# P450_FJ_P_A_V2_3_F.net
KiCad netlist of a schematic drawn in Altium Designer
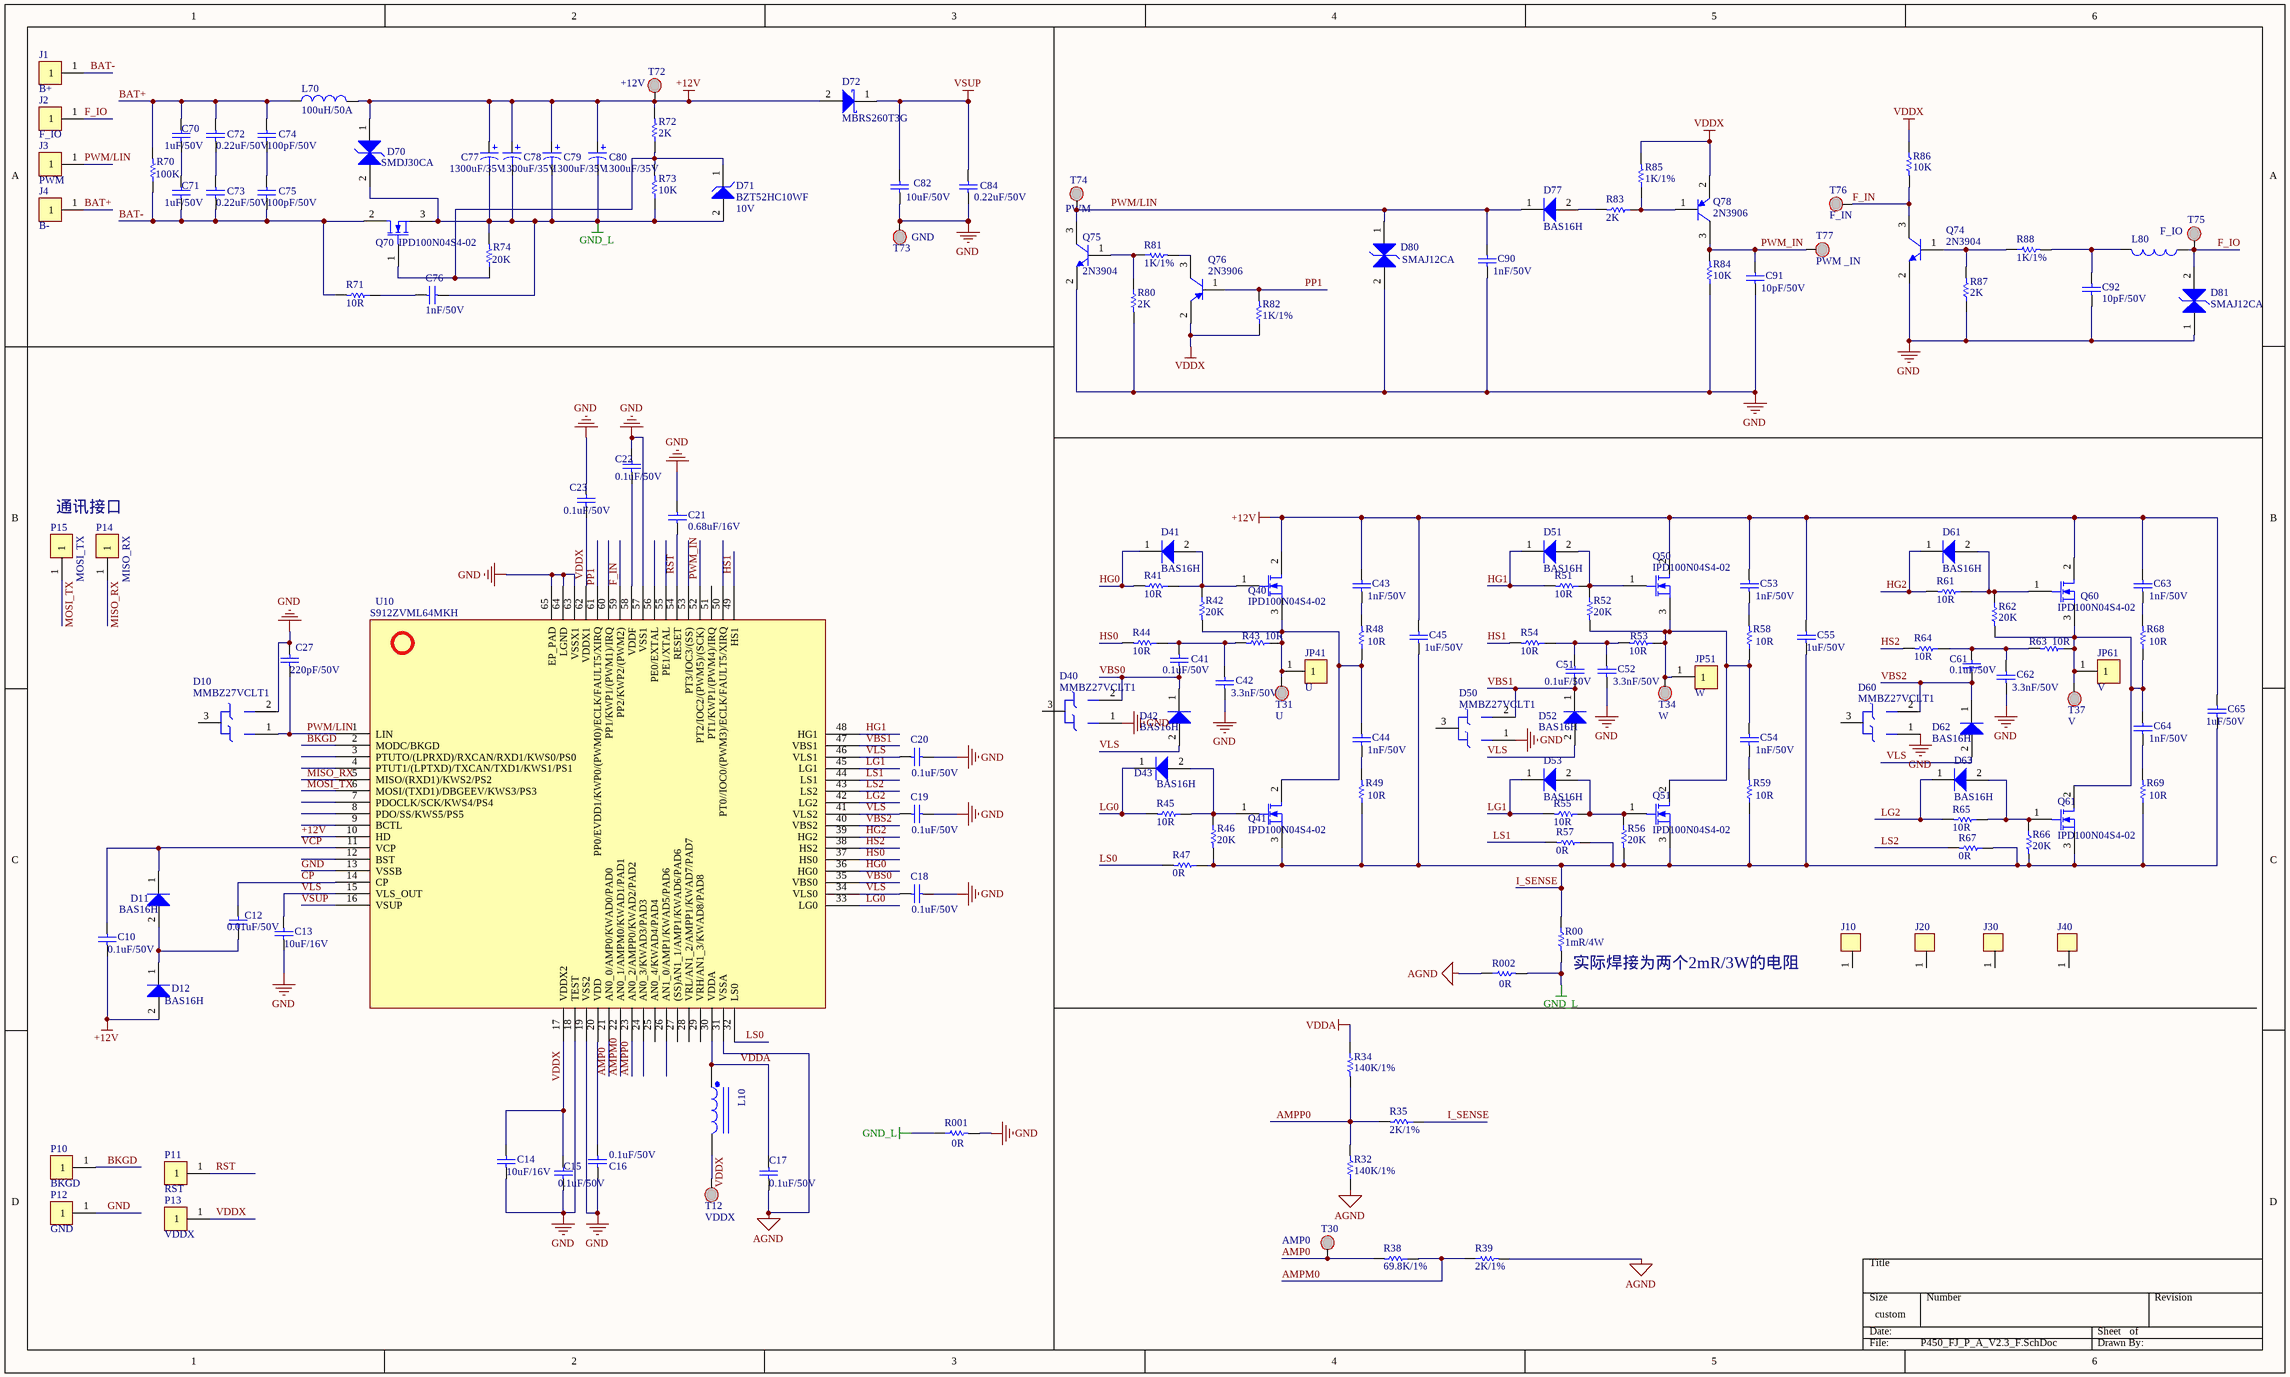
[diagram p0: P450_FJ_P_A_V2.3_F.SchDoc]

(export (version "E")
  (design (tool "Eeschema 10.0.6"))
  (components
    (comp (ref "C10")
      (value "0.1uF/50V")
      (footprint "0603")
      (description "Capacitor")
      (fields (field (name "PUBLISHER") "Altium Limited"))
      (libsource (lib "Miscellaneous Devices") (part "Cap"))
    )
    (comp (ref "C12")
      (value "0.01uF/50V")
      (footprint "0603")
      (description "Capacitor")
      (fields (field (name "PUBLISHER") "Altium Limited"))
      (libsource (lib "Miscellaneous Devices") (part "Cap"))
    )
    (comp (ref "C13")
      (value "10uF/16V")
      (footprint "0805")
      (description "Capacitor")
      (fields (field (name "PUBLISHER") "Altium Limited"))
      (libsource (lib "Miscellaneous Devices") (part "Cap"))
    )
    (comp (ref "C14")
      (value "10uF/16V")
      (footprint "0805")
      (description "Capacitor")
      (fields (field (name "PUBLISHER") "Altium Limited"))
      (libsource (lib "Miscellaneous Devices") (part "Cap"))
    )
    (comp (ref "C15")
      (value "0.1uF/50V")
      (footprint "0603")
      (description "Capacitor")
      (fields (field (name "PUBLISHER") "Altium Limited"))
      (libsource (lib "Miscellaneous Devices") (part "Cap"))
    )
    (comp (ref "C16")
      (value "0.1uF/50V")
      (footprint "0603")
      (description "Capacitor")
      (fields (field (name "PUBLISHER") "Altium Limited"))
      (libsource (lib "Miscellaneous Devices") (part "Cap"))
    )
    (comp (ref "C17")
      (value "0.1uF/50V")
      (footprint "0603")
      (description "Capacitor")
      (fields (field (name "PUBLISHER") "Altium Limited"))
      (libsource (lib "Miscellaneous Devices") (part "Cap"))
    )
    (comp (ref "C18")
      (value "0.1uF/50V")
      (footprint "0603")
      (description "Capacitor")
      (fields (field (name "PUBLISHER") "Altium Limited"))
      (libsource (lib "Miscellaneous Devices") (part "Cap"))
    )
    (comp (ref "C19")
      (value "0.1uF/50V")
      (footprint "0603")
      (description "Capacitor")
      (fields (field (name "PUBLISHER") "Altium Limited"))
      (libsource (lib "Miscellaneous Devices") (part "Cap"))
    )
    (comp (ref "C20")
      (value "0.1uF/50V")
      (footprint "0603")
      (description "Capacitor")
      (fields (field (name "PUBLISHER") "Altium Limited"))
      (libsource (lib "Miscellaneous Devices") (part "Cap"))
    )
    (comp (ref "C21")
      (value "0.68uF/16V")
      (footprint "0603")
      (description "Capacitor")
      (fields (field (name "PUBLISHER") "Altium Limited"))
      (libsource (lib "Miscellaneous Devices") (part "Cap"))
    )
    (comp (ref "C22")
      (value "0.1uF/50V")
      (footprint "0603")
      (description "Capacitor")
      (fields (field (name "PUBLISHER") "Altium Limited"))
      (libsource (lib "Miscellaneous Devices") (part "Cap"))
    )
    (comp (ref "C23")
      (value "0.1uF/50V")
      (footprint "0603")
      (description "Capacitor")
      (fields (field (name "PUBLISHER") "Altium Limited"))
      (libsource (lib "Miscellaneous Devices") (part "Cap"))
    )
    (comp (ref "C27")
      (value "220pF/50V")
      (footprint "0603")
      (description "Capacitor")
      (fields (field (name "PUBLISHER") "Altium Limited"))
      (libsource (lib "Miscellaneous Devices") (part "Cap"))
    )
    (comp (ref "C41")
      (value "0.1uF/50V")
      (footprint "0603")
      (description "Capacitor")
      (fields (field (name "PUBLISHER") "Altium Limited"))
      (libsource (lib "Miscellaneous Devices") (part "Cap"))
    )
    (comp (ref "C42")
      (value "3.3nF/50V")
      (footprint "0603")
      (description "Capacitor")
      (fields (field (name "PUBLISHER") "Altium Limited"))
      (libsource (lib "Miscellaneous Devices") (part "Cap"))
    )
    (comp (ref "C43")
      (value "1nF/50V")
      (footprint "0603")
      (description "Capacitor")
      (fields (field (name "PUBLISHER") "Altium Limited"))
      (libsource (lib "Miscellaneous Devices") (part "Cap"))
    )
    (comp (ref "C44")
      (value "1nF/50V")
      (footprint "0603")
      (description "Capacitor")
      (fields (field (name "PUBLISHER") "Altium Limited"))
      (libsource (lib "Miscellaneous Devices") (part "Cap"))
    )
    (comp (ref "C45")
      (value "1uF/50V")
      (footprint "0805")
      (description "Capacitor")
      (fields (field (name "PUBLISHER") "Altium Limited"))
      (libsource (lib "Miscellaneous Devices") (part "Cap"))
    )
    (comp (ref "C51")
      (value "0.1uF/50V")
      (footprint "0603")
      (description "Capacitor")
      (fields (field (name "PUBLISHER") "Altium Limited"))
      (libsource (lib "Miscellaneous Devices") (part "Cap"))
    )
    (comp (ref "C52")
      (value "3.3nF/50V")
      (footprint "0603")
      (description "Capacitor")
      (fields (field (name "PUBLISHER") "Altium Limited"))
      (libsource (lib "Miscellaneous Devices") (part "Cap"))
    )
    (comp (ref "C53")
      (value "1nF/50V")
      (footprint "0603")
      (description "Capacitor")
      (fields (field (name "PUBLISHER") "Altium Limited"))
      (libsource (lib "Miscellaneous Devices") (part "Cap"))
    )
    (comp (ref "C54")
      (value "1nF/50V")
      (footprint "0603")
      (description "Capacitor")
      (fields (field (name "PUBLISHER") "Altium Limited"))
      (libsource (lib "Miscellaneous Devices") (part "Cap"))
    )
    (comp (ref "C55")
      (value "1uF/50V")
      (footprint "0805")
      (description "Capacitor")
      (fields (field (name "PUBLISHER") "Altium Limited"))
      (libsource (lib "Miscellaneous Devices") (part "Cap"))
    )
    (comp (ref "C61")
      (value "0.1uF/50V")
      (footprint "0603")
      (description "Capacitor")
      (fields (field (name "PUBLISHER") "Altium Limited"))
      (libsource (lib "Miscellaneous Devices") (part "Cap"))
    )
    (comp (ref "C62")
      (value "3.3nF/50V")
      (footprint "0603")
      (description "Capacitor")
      (fields (field (name "PUBLISHER") "Altium Limited"))
      (libsource (lib "Miscellaneous Devices") (part "Cap"))
    )
    (comp (ref "C63")
      (value "1nF/50V")
      (footprint "0603")
      (description "Capacitor")
      (fields (field (name "PUBLISHER") "Altium Limited"))
      (libsource (lib "Miscellaneous Devices") (part "Cap"))
    )
    (comp (ref "C64")
      (value "1nF/50V")
      (footprint "0603")
      (description "Capacitor")
      (fields (field (name "PUBLISHER") "Altium Limited"))
      (libsource (lib "Miscellaneous Devices") (part "Cap"))
    )
    (comp (ref "C65")
      (value "1uF/50V")
      (footprint "0805")
      (description "Capacitor")
      (fields (field (name "PUBLISHER") "Altium Limited"))
      (libsource (lib "Miscellaneous Devices") (part "Cap"))
    )
    (comp (ref "C70")
      (value "1uF/50V")
      (footprint "0805")
      (description "Capacitor")
      (fields (field (name "PUBLISHER") "Altium Limited"))
      (libsource (lib "Miscellaneous Devices") (part "Cap"))
    )
    (comp (ref "C71")
      (value "1uF/50V")
      (footprint "0805")
      (description "Capacitor")
      (fields (field (name "PUBLISHER") "Altium Limited"))
      (libsource (lib "Miscellaneous Devices") (part "Cap"))
    )
    (comp (ref "C72")
      (value "0.22uF/50V")
      (footprint "0805")
      (description "Capacitor")
      (fields (field (name "PUBLISHER") "Altium Limited"))
      (libsource (lib "Miscellaneous Devices") (part "Cap"))
    )
    (comp (ref "C73")
      (value "0.22uF/50V")
      (footprint "0805")
      (description "Capacitor")
      (fields (field (name "PUBLISHER") "Altium Limited"))
      (libsource (lib "Miscellaneous Devices") (part "Cap"))
    )
    (comp (ref "C74")
      (value "100pF/50V")
      (footprint "0805")
      (description "Capacitor")
      (fields (field (name "PUBLISHER") "Altium Limited"))
      (libsource (lib "Miscellaneous Devices") (part "Cap"))
    )
    (comp (ref "C75")
      (value "100pF/50V")
      (footprint "0805")
      (description "Capacitor")
      (fields (field (name "PUBLISHER") "Altium Limited"))
      (libsource (lib "Miscellaneous Devices") (part "Cap"))
    )
    (comp (ref "C76")
      (value "1nF/50V")
      (footprint "0603")
      (description "Capacitor")
      (fields (field (name "PUBLISHER") "Altium Limited"))
      (libsource (lib "Miscellaneous Devices") (part "Cap"))
    )
    (comp (ref "C77")
      (value "1300uF/35V")
      (footprint "RB5.0")
      (description "EGPD350E__132MK20H")
      (fields (field (name "PUBLISHER") "Altium Limited"))
      (libsource (lib "Miscellaneous Devices") (part "Cap Pol1"))
    )
    (comp (ref "C78")
      (value "1300uF/35V")
      (footprint "RB5.0")
      (description "EGPD350E__132MK20H")
      (fields (field (name "PUBLISHER") "Altium Limited"))
      (libsource (lib "Miscellaneous Devices") (part "Cap Pol1"))
    )
    (comp (ref "C79")
      (value "1300uF/35V")
      (footprint "RB5.0")
      (description "EGPD350E__132MK20H")
      (fields (field (name "PUBLISHER") "Altium Limited"))
      (libsource (lib "Miscellaneous Devices") (part "Cap Pol1"))
    )
    (comp (ref "C80")
      (value "1300uF/35V")
      (footprint "RB5.0")
      (description "EGPD350E__132MK20H")
      (fields (field (name "PUBLISHER") "Altium Limited"))
      (libsource (lib "Miscellaneous Devices") (part "Cap Pol1"))
    )
    (comp (ref "C82")
      (value "10uF/50V")
      (footprint "1210")
      (description "Capacitor")
      (fields (field (name "PUBLISHER") "Altium Limited"))
      (libsource (lib "Miscellaneous Devices") (part "Cap"))
    )
    (comp (ref "C84")
      (value "0.22uF/50V")
      (footprint "0805")
      (description "Capacitor")
      (fields (field (name "PUBLISHER") "Altium Limited"))
      (libsource (lib "Miscellaneous Devices") (part "Cap"))
    )
    (comp (ref "C90")
      (value "1nF/50V")
      (footprint "0603")
      (description "Capacitor")
      (fields (field (name "PUBLISHER") "Altium Limited"))
      (libsource (lib "Miscellaneous Devices") (part "Cap"))
    )
    (comp (ref "C91")
      (value "10pF/50V")
      (footprint "0603")
      (description "Capacitor")
      (fields (field (name "PUBLISHER") "Altium Limited"))
      (libsource (lib "Miscellaneous Devices") (part "Cap"))
    )
    (comp (ref "C92")
      (value "10pF/50V")
      (footprint "0603")
      (description "Capacitor")
      (fields (field (name "PUBLISHER") "Altium Limited"))
      (libsource (lib "Miscellaneous Devices") (part "Cap"))
    )
    (comp (ref "D10")
      (value "MMBZ27VCLT1")
      (footprint "SOT-23T")
      (description "D_TVS")
      (libsource (lib "SCH_LIB") (part "MMBZ27VCLT1"))
    )
    (comp (ref "D11")
      (value "BAS16H")
      (footprint "SOD323")
      (description "Default Diode")
      (fields (field (name "PUBLISHER") "Altium Limited"))
      (libsource (lib "LIN_12V-3P") (part "Diode"))
    )
    (comp (ref "D12")
      (value "BAS16H")
      (footprint "SOD323")
      (description "Default Diode")
      (fields (field (name "PUBLISHER") "Altium Limited"))
      (libsource (lib "LIN_12V-3P") (part "Diode"))
    )
    (comp (ref "D40")
      (value "MMBZ27VCLT1")
      (footprint "SOT-23T")
      (description "D_TVS")
      (libsource (lib "SCH_LIB") (part "MMBZ27VCLT1"))
    )
    (comp (ref "D41")
      (value "BAS16H")
      (footprint "SOD323")
      (description "Default Diode")
      (fields (field (name "PUBLISHER") "Altium Limited"))
      (libsource (lib "LIN_12V-3P") (part "Diode"))
    )
    (comp (ref "D42")
      (value "BAS16H")
      (footprint "SOD323")
      (description "Default Diode")
      (fields (field (name "PUBLISHER") "Altium Limited"))
      (libsource (lib "LIN_12V-3P") (part "Diode"))
    )
    (comp (ref "D43")
      (value "BAS16H")
      (footprint "SOD323")
      (description "Default Diode")
      (fields (field (name "PUBLISHER") "Altium Limited"))
      (libsource (lib "LIN_12V-3P") (part "Diode"))
    )
    (comp (ref "D50")
      (value "MMBZ27VCLT1")
      (footprint "SOT-23T")
      (description "D_TVS")
      (libsource (lib "SCH_LIB") (part "MMBZ27VCLT1"))
    )
    (comp (ref "D51")
      (value "BAS16H")
      (footprint "SOD323")
      (description "Default Diode")
      (fields (field (name "PUBLISHER") "Altium Limited"))
      (libsource (lib "LIN_12V-3P") (part "Diode"))
    )
    (comp (ref "D52")
      (value "BAS16H")
      (footprint "SOD323")
      (description "Default Diode")
      (fields (field (name "PUBLISHER") "Altium Limited"))
      (libsource (lib "LIN_12V-3P") (part "Diode"))
    )
    (comp (ref "D53")
      (value "BAS16H")
      (footprint "SOD323")
      (description "Default Diode")
      (fields (field (name "PUBLISHER") "Altium Limited"))
      (libsource (lib "LIN_12V-3P") (part "Diode"))
    )
    (comp (ref "D60")
      (value "MMBZ27VCLT1")
      (footprint "SOT-23T")
      (description "D_TVS")
      (libsource (lib "SCH_LIB") (part "MMBZ27VCLT1"))
    )
    (comp (ref "D61")
      (value "BAS16H")
      (footprint "SOD323")
      (description "Default Diode")
      (fields (field (name "PUBLISHER") "Altium Limited"))
      (libsource (lib "LIN_12V-3P") (part "Diode"))
    )
    (comp (ref "D62")
      (value "BAS16H")
      (footprint "SOD323")
      (description "Default Diode")
      (fields (field (name "PUBLISHER") "Altium Limited"))
      (libsource (lib "LIN_12V-3P") (part "Diode"))
    )
    (comp (ref "D63")
      (value "BAS16H")
      (footprint "SOD323")
      (description "Default Diode")
      (fields (field (name "PUBLISHER") "Altium Limited"))
      (libsource (lib "LIN_12V-3P") (part "Diode"))
    )
    (comp (ref "D70")
      (value "SMDJ30CA")
      (footprint "DO-214AB")
      (description "Tunnel Diode - RLC Model")
      (fields (field (name "PUBLISHER") "Altium Limited"))
      (libsource (lib "P500_FJ_P_B_V1.1_SCH") (part "TVS_D"))
    )
    (comp (ref "D71")
      (value "BZT52HC10WF")
      (footprint "SOD123")
      (description "Zener Diode")
      (fields (field (name "ALTIUM_UNNAMED_1") "10V") (field (name "PUBLISHER") "Altium Limited"))
      (libsource (lib "LIN_12V-3P") (part "D Zener"))
    )
    (comp (ref "D72")
      (value "MBRS260T3G")
      (footprint "SMB403A-03")
      (description "Silicon RF Schottky Diode for Mixer Applications in the VHF/UHF Range")
      (fields (field (name "PUBLISHER") "Altium Limited"))
      (libsource (lib "LIN_12V-3P") (part "Diode BAT17"))
    )
    (comp (ref "D77")
      (value "BAS16H")
      (footprint "SOD323")
      (description "Default Diode")
      (fields (field (name "PUBLISHER") "Altium Limited"))
      (libsource (lib "LIN_12V-3P") (part "Diode"))
    )
    (comp (ref "D80")
      (value "SMAJ12CA")
      (footprint "SMA/DO-214AC")
      (description "Tunnel Diode - RLC Model")
      (fields (field (name "PUBLISHER") "Altium Limited"))
      (libsource (lib "P500_FJ_P_B_V1.1_SCH") (part "TVS_D"))
    )
    (comp (ref "D81")
      (value "SMAJ12CA")
      (footprint "SMA/DO-214AC")
      (description "Tunnel Diode - RLC Model")
      (fields (field (name "PUBLISHER") "Altium Limited"))
      (libsource (lib "P500_FJ_P_B_V1.1_SCH") (part "TVS_D"))
    )
    (comp (ref "J1")
      (value "B+")
      (footprint "POWER")
      (description "Header")
      (libsource (lib "SCH_LIB") (part "J1X1"))
    )
    (comp (ref "J2")
      (value "F_IO")
      (footprint "IO")
      (description "Header")
      (libsource (lib "SCH_LIB") (part "J1X1"))
    )
    (comp (ref "J3")
      (value "PWM")
      (footprint "IO")
      (description "Header")
      (libsource (lib "SCH_LIB") (part "J1X1"))
    )
    (comp (ref "J4")
      (value "B-")
      (footprint "POWER")
      (description "Header")
      (libsource (lib "SCH_LIB") (part "J1X1"))
    )
    (comp (ref "J10") (value "M3") (footprint "PADS") (libsource (lib "P450_FJ_P_A_V1.0_SCH") (part "CON1")))
    (comp (ref "J20") (value "M3") (footprint "PADS") (libsource (lib "P450_FJ_P_A_V1.0_SCH") (part "CON1")))
    (comp (ref "J30") (value "M3") (footprint "PADS") (libsource (lib "P450_FJ_P_A_V1.0_SCH") (part "CON1")))
    (comp (ref "J40") (value "M3") (footprint "PADS") (libsource (lib "P450_FJ_P_A_V1.0_SCH") (part "CON1")))
    (comp (ref "JP41")
      (value "U")
      (footprint "UVW1")
      (description "Header")
      (libsource (lib "SCH_LIB") (part "HDR 1X1"))
    )
    (comp (ref "JP51")
      (value "W")
      (footprint "UVW1")
      (description "Header")
      (libsource (lib "SCH_LIB") (part "HDR 1X1"))
    )
    (comp (ref "JP61")
      (value "V")
      (footprint "UVW1")
      (description "Header")
      (libsource (lib "SCH_LIB") (part "HDR 1X1"))
    )
    (comp (ref "L10")
      (value "KMZ1608YHR102BTD")
      (footprint "0603")
      (description "Magnetic-Core Inductor with Winding Polarity Marking")
      (fields (field (name "PUBLISHER") "Altium Limited"))
      (libsource (lib "Miscellaneous Devices") (part "Inductor Iron Dot"))
    )
    (comp (ref "L70")
      (value "100uH/50A")
      (footprint "L10-20")
      (description "AFDIGOQQQQ092R5MR1")
      (fields (field (name "PUBLISHER") "Altium Limited"))
      (libsource (lib "Miscellaneous Devices") (part "Inductor"))
    )
    (comp (ref "L80")
      (value "KMZ1608YHR102BTD")
      (footprint "0603")
      (description "Inductor")
      (fields (field (name "PUBLISHER") "Altium Limited"))
      (libsource (lib "Miscellaneous Devices") (part "Inductor"))
    )
    (comp (ref "P10")
      (value "BKGD")
      (footprint "TEST_S1")
      (description "Header")
      (libsource (lib "") (part "Header1_1"))
    )
    (comp (ref "P11")
      (value "RST")
      (footprint "TEST_S1")
      (description "Header")
      (libsource (lib "") (part "Header1_1"))
    )
    (comp (ref "P12")
      (value "GND")
      (footprint "TEST_S1")
      (description "Header")
      (libsource (lib "") (part "Header1_1"))
    )
    (comp (ref "P13")
      (value "VDDX")
      (footprint "TEST_S2")
      (description "Header")
      (libsource (lib "") (part "Header1_1"))
    )
    (comp (ref "P14")
      (value "MISO_RX")
      (footprint "TEST_S1")
      (description "Header")
      (libsource (lib "SCH_LIB") (part "Header1"))
    )
    (comp (ref "P15")
      (value "MOSI_TX")
      (footprint "TEST_S1")
      (description "Header")
      (libsource (lib "SCH_LIB") (part "Header1"))
    )
    (comp (ref "Q40")
      (value "IPD100N04S4-02")
      (footprint "TO-252")
      (description "N-Channel MOSFET")
      (fields (field (name "PUBLISHER") "Altium Limited"))
      (libsource (lib "P500_FJ_P_B_V1.1_SCH") (part "MOSFET-N"))
    )
    (comp (ref "Q41")
      (value "IPD100N04S4-02")
      (footprint "TO-252")
      (description "N-Channel MOSFET")
      (fields (field (name "PUBLISHER") "Altium Limited"))
      (libsource (lib "P500_FJ_P_B_V1.1_SCH") (part "MOSFET-N"))
    )
    (comp (ref "Q50")
      (value "IPD100N04S4-02")
      (footprint "TO-252")
      (description "N-Channel MOSFET")
      (fields (field (name "PUBLISHER") "Altium Limited"))
      (libsource (lib "P500_FJ_P_B_V1.1_SCH") (part "MOSFET-N"))
    )
    (comp (ref "Q51")
      (value "IPD100N04S4-02")
      (footprint "TO-252")
      (description "N-Channel MOSFET")
      (fields (field (name "PUBLISHER") "Altium Limited"))
      (libsource (lib "P500_FJ_P_B_V1.1_SCH") (part "MOSFET-N"))
    )
    (comp (ref "Q60")
      (value "IPD100N04S4-02")
      (footprint "TO-252")
      (description "N-Channel MOSFET")
      (fields (field (name "PUBLISHER") "Altium Limited"))
      (libsource (lib "P500_FJ_P_B_V1.1_SCH") (part "MOSFET-N"))
    )
    (comp (ref "Q61")
      (value "IPD100N04S4-02")
      (footprint "TO-252")
      (description "N-Channel MOSFET")
      (fields (field (name "PUBLISHER") "Altium Limited"))
      (libsource (lib "P500_FJ_P_B_V1.1_SCH") (part "MOSFET-N"))
    )
    (comp (ref "Q70")
      (value "IPD100N04S4-02")
      (footprint "TO-252")
      (description "N-Channel MOSFET")
      (fields (field (name "PUBLISHER") "Altium Limited"))
      (libsource (lib "P500_FJ_P_B_V1.1_SCH") (part "MOSFET-N"))
    )
    (comp (ref "Q74")
      (value "2N3904")
      (footprint "SOT-23T")
      (description "NPN General Purpose Amplifier")
      (fields (field (name "PUBLISHER") "Altium Limited"))
      (libsource (lib "P450_FJ_P_A_V1.0_F") (part "MMBTA06"))
    )
    (comp (ref "Q75")
      (value "2N3904")
      (footprint "SOT-23T")
      (description "NPN General Purpose Amplifier")
      (fields (field (name "PUBLISHER") "Altium Limited"))
      (libsource (lib "P450_FJ_P_A_V1.0_F") (part "MMBTA06"))
    )
    (comp (ref "Q76")
      (value "2N3906")
      (footprint "SOT-23T")
      (description "PNP General Purpose Amplifier")
      (fields (field (name "PUBLISHER") "Altium Limited"))
      (libsource (lib "LIN_12V-3P") (part "2N3906"))
    )
    (comp (ref "Q78")
      (value "2N3906")
      (footprint "SOT-23T")
      (description "PNP General Purpose Amplifier")
      (fields (field (name "PUBLISHER") "Altium Limited"))
      (libsource (lib "LIN_12V-3P") (part "2N3906"))
    )
    (comp (ref "R00")
      (value "1mR/4W")
      (footprint "1050")
      (description "Resistor")
      (fields (field (name "Comment") "LRS1050FEDHR001") (field (name "PUBLISHER") "Altium Limited"))
      (libsource (lib "Miscellaneous Devices") (part "Res1"))
    )
    (comp (ref "R001")
      (value "0R")
      (footprint "0603")
      (description "Resistor")
      (fields (field (name "PUBLISHER") "Altium Limited"))
      (libsource (lib "Miscellaneous Devices") (part "Res1"))
    )
    (comp (ref "R002")
      (value "0R")
      (footprint "0603")
      (description "Resistor")
      (fields (field (name "PUBLISHER") "Altium Limited"))
      (libsource (lib "Miscellaneous Devices") (part "Res1"))
    )
    (comp (ref "R32")
      (value "140K/1%")
      (footprint "0603")
      (description "Resistor")
      (fields (field (name "PUBLISHER") "Altium Limited"))
      (libsource (lib "Miscellaneous Devices") (part "Res1"))
    )
    (comp (ref "R34")
      (value "140K/1%")
      (footprint "0603")
      (description "Resistor")
      (fields (field (name "PUBLISHER") "Altium Limited"))
      (libsource (lib "Miscellaneous Devices") (part "Res1"))
    )
    (comp (ref "R35")
      (value "2K/1%")
      (footprint "0603")
      (description "Resistor")
      (fields (field (name "PUBLISHER") "Altium Limited"))
      (libsource (lib "Miscellaneous Devices") (part "Res1"))
    )
    (comp (ref "R38")
      (value "69.8K/1%")
      (footprint "0603")
      (description "Resistor")
      (fields (field (name "PUBLISHER") "Altium Limited"))
      (libsource (lib "Miscellaneous Devices") (part "Res1"))
    )
    (comp (ref "R39")
      (value "2K/1%")
      (footprint "0603")
      (description "Resistor")
      (fields (field (name "PUBLISHER") "Altium Limited"))
      (libsource (lib "Miscellaneous Devices") (part "Res1"))
    )
    (comp (ref "R41")
      (value "10R")
      (footprint "0603")
      (description "Resistor")
      (fields (field (name "PUBLISHER") "Altium Limited"))
      (libsource (lib "Miscellaneous Devices") (part "Res1"))
    )
    (comp (ref "R42")
      (value "20K")
      (footprint "0603")
      (description "Resistor")
      (fields (field (name "PUBLISHER") "Altium Limited"))
      (libsource (lib "Miscellaneous Devices") (part "Res1"))
    )
    (comp (ref "R43")
      (value "10R")
      (footprint "0603")
      (description "Resistor")
      (fields (field (name "PUBLISHER") "Altium Limited"))
      (libsource (lib "Miscellaneous Devices") (part "Res1"))
    )
    (comp (ref "R44")
      (value "10R")
      (footprint "0603")
      (description "Resistor")
      (fields (field (name "PUBLISHER") "Altium Limited"))
      (libsource (lib "Miscellaneous Devices") (part "Res1"))
    )
    (comp (ref "R45")
      (value "10R")
      (footprint "0603")
      (description "Resistor")
      (fields (field (name "PUBLISHER") "Altium Limited"))
      (libsource (lib "Miscellaneous Devices") (part "Res1"))
    )
    (comp (ref "R46")
      (value "20K")
      (footprint "0603")
      (description "Resistor")
      (fields (field (name "PUBLISHER") "Altium Limited"))
      (libsource (lib "Miscellaneous Devices") (part "Res1"))
    )
    (comp (ref "R47")
      (value "0R")
      (footprint "0603")
      (description "Resistor")
      (fields (field (name "PUBLISHER") "Altium Limited"))
      (libsource (lib "Miscellaneous Devices") (part "Res1"))
    )
    (comp (ref "R48")
      (value "10R")
      (footprint "0603")
      (description "Resistor")
      (fields (field (name "PUBLISHER") "Altium Limited"))
      (libsource (lib "Miscellaneous Devices") (part "Res1"))
    )
    (comp (ref "R49")
      (value "10R")
      (footprint "0603")
      (description "Resistor")
      (fields (field (name "PUBLISHER") "Altium Limited"))
      (libsource (lib "Miscellaneous Devices") (part "Res1"))
    )
    (comp (ref "R51")
      (value "10R")
      (footprint "0603")
      (description "Resistor")
      (fields (field (name "PUBLISHER") "Altium Limited"))
      (libsource (lib "Miscellaneous Devices") (part "Res1"))
    )
    (comp (ref "R52")
      (value "20K")
      (footprint "0603")
      (description "Resistor")
      (fields (field (name "PUBLISHER") "Altium Limited"))
      (libsource (lib "Miscellaneous Devices") (part "Res1"))
    )
    (comp (ref "R53")
      (value "10R")
      (footprint "0603")
      (description "Resistor")
      (fields (field (name "PUBLISHER") "Altium Limited"))
      (libsource (lib "Miscellaneous Devices") (part "Res1"))
    )
    (comp (ref "R54")
      (value "10R")
      (footprint "0603")
      (description "Resistor")
      (fields (field (name "PUBLISHER") "Altium Limited"))
      (libsource (lib "Miscellaneous Devices") (part "Res1"))
    )
    (comp (ref "R55")
      (value "10R")
      (footprint "0603")
      (description "Resistor")
      (fields (field (name "PUBLISHER") "Altium Limited"))
      (libsource (lib "Miscellaneous Devices") (part "Res1"))
    )
    (comp (ref "R56")
      (value "20K")
      (footprint "0603")
      (description "Resistor")
      (fields (field (name "PUBLISHER") "Altium Limited"))
      (libsource (lib "Miscellaneous Devices") (part "Res1"))
    )
    (comp (ref "R57")
      (value "0R")
      (footprint "0603")
      (description "Resistor")
      (fields (field (name "PUBLISHER") "Altium Limited"))
      (libsource (lib "Miscellaneous Devices") (part "Res1"))
    )
    (comp (ref "R58")
      (value "10R")
      (footprint "0603")
      (description "Resistor")
      (fields (field (name "PUBLISHER") "Altium Limited"))
      (libsource (lib "Miscellaneous Devices") (part "Res1"))
    )
    (comp (ref "R59")
      (value "10R")
      (footprint "0603")
      (description "Resistor")
      (fields (field (name "PUBLISHER") "Altium Limited"))
      (libsource (lib "Miscellaneous Devices") (part "Res1"))
    )
    (comp (ref "R61")
      (value "10R")
      (footprint "0603")
      (description "Resistor")
      (fields (field (name "PUBLISHER") "Altium Limited"))
      (libsource (lib "Miscellaneous Devices") (part "Res1"))
    )
    (comp (ref "R62")
      (value "20K")
      (footprint "0603")
      (description "Resistor")
      (fields (field (name "PUBLISHER") "Altium Limited"))
      (libsource (lib "Miscellaneous Devices") (part "Res1"))
    )
    (comp (ref "R63")
      (value "10R")
      (footprint "0603")
      (description "Resistor")
      (fields (field (name "PUBLISHER") "Altium Limited"))
      (libsource (lib "Miscellaneous Devices") (part "Res1"))
    )
    (comp (ref "R64")
      (value "10R")
      (footprint "0603")
      (description "Resistor")
      (fields (field (name "PUBLISHER") "Altium Limited"))
      (libsource (lib "Miscellaneous Devices") (part "Res1"))
    )
    (comp (ref "R65")
      (value "10R")
      (footprint "0603")
      (description "Resistor")
      (fields (field (name "PUBLISHER") "Altium Limited"))
      (libsource (lib "Miscellaneous Devices") (part "Res1"))
    )
    (comp (ref "R66")
      (value "20K")
      (footprint "0603")
      (description "Resistor")
      (fields (field (name "PUBLISHER") "Altium Limited"))
      (libsource (lib "Miscellaneous Devices") (part "Res1"))
    )
    (comp (ref "R67")
      (value "0R")
      (footprint "0603")
      (description "Resistor")
      (fields (field (name "PUBLISHER") "Altium Limited"))
      (libsource (lib "Miscellaneous Devices") (part "Res1"))
    )
    (comp (ref "R68")
      (value "10R")
      (footprint "0603")
      (description "Resistor")
      (fields (field (name "PUBLISHER") "Altium Limited"))
      (libsource (lib "Miscellaneous Devices") (part "Res1"))
    )
    (comp (ref "R69")
      (value "10R")
      (footprint "0603")
      (description "Resistor")
      (fields (field (name "PUBLISHER") "Altium Limited"))
      (libsource (lib "Miscellaneous Devices") (part "Res1"))
    )
    (comp (ref "R70")
      (value "100K")
      (footprint "0805")
      (description "Resistor")
      (fields (field (name "PUBLISHER") "Altium Limited"))
      (libsource (lib "Miscellaneous Devices") (part "Res1"))
    )
    (comp (ref "R71")
      (value "10R")
      (footprint "0603")
      (description "Resistor")
      (fields (field (name "PUBLISHER") "Altium Limited"))
      (libsource (lib "Miscellaneous Devices") (part "Res1"))
    )
    (comp (ref "R72")
      (value "2K")
      (footprint "0603")
      (description "Resistor")
      (fields (field (name "PUBLISHER") "Altium Limited"))
      (libsource (lib "Miscellaneous Devices") (part "Res1"))
    )
    (comp (ref "R73")
      (value "10K")
      (footprint "0603")
      (description "Resistor")
      (fields (field (name "PUBLISHER") "Altium Limited"))
      (libsource (lib "Miscellaneous Devices") (part "Res1"))
    )
    (comp (ref "R74")
      (value "20K")
      (footprint "0603")
      (description "Resistor")
      (fields (field (name "PUBLISHER") "Altium Limited"))
      (libsource (lib "Miscellaneous Devices") (part "Res1"))
    )
    (comp (ref "R80")
      (value "2K")
      (footprint "0603")
      (description "Resistor")
      (fields (field (name "PUBLISHER") "Altium Limited"))
      (libsource (lib "Miscellaneous Devices") (part "Res1"))
    )
    (comp (ref "R81")
      (value "1K/1%")
      (footprint "0603")
      (description "Resistor")
      (fields (field (name "PUBLISHER") "Altium Limited"))
      (libsource (lib "Miscellaneous Devices") (part "Res1"))
    )
    (comp (ref "R82")
      (value "1K/1%")
      (footprint "0603")
      (description "Resistor")
      (fields (field (name "PUBLISHER") "Altium Limited"))
      (libsource (lib "Miscellaneous Devices") (part "Res1"))
    )
    (comp (ref "R83")
      (value "2K")
      (footprint "0603")
      (description "Resistor")
      (fields (field (name "PUBLISHER") "Altium Limited"))
      (libsource (lib "Miscellaneous Devices") (part "Res1"))
    )
    (comp (ref "R84")
      (value "10K")
      (footprint "0603")
      (description "Resistor")
      (fields (field (name "PUBLISHER") "Altium Limited"))
      (libsource (lib "Miscellaneous Devices") (part "Res1"))
    )
    (comp (ref "R85")
      (value "1K/1%")
      (footprint "0603")
      (description "Resistor")
      (fields (field (name "PUBLISHER") "Altium Limited"))
      (libsource (lib "Miscellaneous Devices") (part "Res1"))
    )
    (comp (ref "R86")
      (value "10K")
      (footprint "0603")
      (description "Resistor")
      (fields (field (name "PUBLISHER") "Altium Limited"))
      (libsource (lib "Miscellaneous Devices") (part "Res1"))
    )
    (comp (ref "R87")
      (value "2K")
      (footprint "0603")
      (description "Resistor")
      (fields (field (name "PUBLISHER") "Altium Limited"))
      (libsource (lib "Miscellaneous Devices") (part "Res1"))
    )
    (comp (ref "R88")
      (value "1K/1%")
      (footprint "0603")
      (description "Resistor")
      (fields (field (name "PUBLISHER") "Altium Limited"))
      (libsource (lib "Miscellaneous Devices") (part "Res1"))
    )
    (comp (ref "T12") (value "VDDX") (footprint "TEST_S") (libsource (lib "LIN_12V-3P") (part "TEST")))
    (comp (ref "T30") (value "AMP0") (footprint "TEST-1") (libsource (lib "LIN_12V-3P") (part "TEST")))
    (comp (ref "T31") (value "U") (footprint "TEST_S") (libsource (lib "LIN_12V-3P") (part "TEST")))
    (comp (ref "T34") (value "W") (footprint "TEST_S") (libsource (lib "LIN_12V-3P") (part "TEST")))
    (comp (ref "T37") (value "V") (footprint "TEST_S") (libsource (lib "LIN_12V-3P") (part "TEST")))
    (comp (ref "T72") (value "+12V") (footprint "TEST_S") (libsource (lib "LIN_12V-3P") (part "TEST")))
    (comp (ref "T73") (value "GND") (footprint "TEST_S") (libsource (lib "LIN_12V-3P") (part "TEST")))
    (comp (ref "T74") (value "PWM") (footprint "TEST_S") (libsource (lib "LIN_12V-3P") (part "TEST")))
    (comp (ref "T75") (value "F_IO") (footprint "TEST_S") (libsource (lib "LIN_12V-3P") (part "TEST")))
    (comp (ref "T76") (value "F_IN") (footprint "TEST-1") (libsource (lib "LIN_12V-3P") (part "TEST")))
    (comp (ref "T77") (value "PWM _IN") (footprint "TEST-1") (libsource (lib "LIN_12V-3P") (part "TEST")))
    (comp (ref "U10")
      (value "S912ZVML64MKH")
      (footprint "64LQFP")
      (description "MCU")
      (libsource (lib "SCH_LIB") (part "PC9S12ZVML12MKH_1"))
    )
  )
  (nets
    (net (code "1") (name "+12V") (class "Default")
      (node (ref "C10") (pin "2") (pinfunction "2_2") (pintype "passive"))
      (node (ref "C43") (pin "2") (pinfunction "2_2") (pintype "passive"))
      (node (ref "C45") (pin "2") (pinfunction "2_2") (pintype "passive"))
      (node (ref "C53") (pin "2") (pinfunction "2_2") (pintype "passive"))
      (node (ref "C55") (pin "2") (pinfunction "2_2") (pintype "passive"))
      (node (ref "C63") (pin "2") (pinfunction "2_2") (pintype "passive"))
      (node (ref "C65") (pin "2") (pinfunction "2_2") (pintype "passive"))
      (node (ref "C77") (pin "1") (pinfunction "1_1") (pintype "passive"))
      (node (ref "C78") (pin "1") (pinfunction "1_1") (pintype "passive"))
      (node (ref "C79") (pin "1") (pinfunction "1_1") (pintype "passive"))
      (node (ref "C80") (pin "1") (pinfunction "1_1") (pintype "passive"))
      (node (ref "D12") (pin "2") (pinfunction "A_2") (pintype "passive"))
      (node (ref "D70") (pin "1") (pinfunction "1_1") (pintype "passive"))
      (node (ref "D72") (pin "2") (pinfunction "A_2") (pintype "passive"))
      (node (ref "L70") (pin "2") (pinfunction "2_2") (pintype "passive"))
      (node (ref "Q40") (pin "2") (pinfunction "D_2") (pintype "passive"))
      (node (ref "Q50") (pin "2") (pinfunction "D_2") (pintype "passive"))
      (node (ref "Q60") (pin "2") (pinfunction "D_2") (pintype "passive"))
      (node (ref "R72") (pin "2") (pinfunction "2_2") (pintype "passive"))
      (node (ref "T72") (pin "1") (pinfunction "1_1") (pintype "passive"))
      (node (ref "U10") (pin "10") (pinfunction "HD_10") (pintype "passive"))
    )
    (net (code "2") (name "/AMP0") (class "Default")
      (node (ref "R38") (pin "2") (pinfunction "2_2") (pintype "passive"))
      (node (ref "T30") (pin "1") (pinfunction "1_1") (pintype "passive"))
      (node (ref "U10") (pin "21") (pinfunction "AN0_0/AMP0/KWAD0/PAD0_21") (pintype "passive"))
    )
    (net (code "3") (name "/AMPM0") (class "Default")
      (node (ref "R38") (pin "1") (pinfunction "1_1") (pintype "passive"))
      (node (ref "R39") (pin "1") (pinfunction "1_1") (pintype "passive"))
      (node (ref "U10") (pin "22") (pinfunction "AN0_1/AMPM0/KWAD1/PAD1_22") (pintype "passive"))
    )
    (net (code "4") (name "/AMPP0") (class "Default")
      (node (ref "R32") (pin "2") (pinfunction "2_2") (pintype "passive"))
      (node (ref "R34") (pin "2") (pinfunction "2_2") (pintype "passive"))
      (node (ref "R35") (pin "2") (pinfunction "2_2") (pintype "passive"))
      (node (ref "U10") (pin "23") (pinfunction "AN0_2/AMPP0/KWAD2/PAD2_23") (pintype "passive"))
    )
    (net (code "5") (name "/BAT+") (class "Default")
      (node (ref "C70") (pin "2") (pinfunction "2_2") (pintype "passive"))
      (node (ref "C72") (pin "2") (pinfunction "2_2") (pintype "passive"))
      (node (ref "C74") (pin "2") (pinfunction "2_2") (pintype "passive"))
      (node (ref "J4") (pin "1") (pinfunction "1_1") (pintype "passive"))
      (node (ref "L70") (pin "1") (pinfunction "1_1") (pintype "passive"))
      (node (ref "R70") (pin "2") (pinfunction "2_2") (pintype "passive"))
    )
    (net (code "6") (name "/BAT-") (class "Default")
      (node (ref "C71") (pin "1") (pinfunction "1_1") (pintype "passive"))
      (node (ref "C73") (pin "1") (pinfunction "1_1") (pintype "passive"))
      (node (ref "C75") (pin "1") (pinfunction "1_1") (pintype "passive"))
      (node (ref "J1") (pin "1") (pinfunction "1_1") (pintype "passive"))
      (node (ref "Q70") (pin "2") (pinfunction "D_2") (pintype "passive"))
      (node (ref "R70") (pin "1") (pinfunction "1_1") (pintype "passive"))
      (node (ref "R71") (pin "2") (pinfunction "2_2") (pintype "passive"))
    )
    (net (code "7") (name "/BKGD") (class "Default")
      (node (ref "P10") (pin "1") (pinfunction "1_1") (pintype "passive"))
      (node (ref "U10") (pin "2") (pinfunction "MODC/BKGD_2") (pintype "passive"))
    )
    (net (code "8") (name "/CP") (class "Default")
      (node (ref "C12") (pin "2") (pinfunction "2_2") (pintype "passive"))
      (node (ref "U10") (pin "14") (pinfunction "CP_14") (pintype "passive"))
    )
    (net (code "9") (name "/F_IN") (class "Default")
      (node (ref "Q74") (pin "3") (pinfunction "C_3") (pintype "passive"))
      (node (ref "R86") (pin "2") (pinfunction "2_2") (pintype "passive"))
      (node (ref "T76") (pin "1") (pinfunction "1_1") (pintype "passive"))
      (node (ref "U10") (pin "59") (pinfunction "PP2/KWP2/(PWM2)_59") (pintype "passive"))
    )
    (net (code "10") (name "/F_IO") (class "Default")
      (node (ref "D81") (pin "2") (pinfunction "2_2") (pintype "passive"))
      (node (ref "J2") (pin "1") (pinfunction "1_1") (pintype "passive"))
      (node (ref "L80") (pin "1") (pinfunction "1_1") (pintype "passive"))
      (node (ref "T75") (pin "1") (pinfunction "1_1") (pintype "passive"))
    )
    (net (code "11") (name "/HG0") (class "Default")
      (node (ref "D41") (pin "1") (pinfunction "C_1") (pintype "passive"))
      (node (ref "R41") (pin "2") (pinfunction "2_2") (pintype "passive"))
      (node (ref "U10") (pin "36") (pinfunction "HG0_36") (pintype "passive"))
    )
    (net (code "12") (name "/HG1") (class "Default")
      (node (ref "D51") (pin "1") (pinfunction "C_1") (pintype "passive"))
      (node (ref "R51") (pin "2") (pinfunction "2_2") (pintype "passive"))
      (node (ref "U10") (pin "48") (pinfunction "HG1_48") (pintype "passive"))
    )
    (net (code "13") (name "/HG2") (class "Default")
      (node (ref "D61") (pin "1") (pinfunction "C_1") (pintype "passive"))
      (node (ref "R61") (pin "2") (pinfunction "2_2") (pintype "passive"))
      (node (ref "U10") (pin "39") (pinfunction "HG2_39") (pintype "passive"))
    )
    (net (code "14") (name "/HS0") (class "Default")
      (node (ref "R44") (pin "2") (pinfunction "2_2") (pintype "passive"))
      (node (ref "U10") (pin "37") (pinfunction "HS0_37") (pintype "passive"))
    )
    (net (code "15") (name "/HS1") (class "Default")
      (node (ref "R54") (pin "2") (pinfunction "2_2") (pintype "passive"))
      (node (ref "U10") (pin "49") (pinfunction "HS1_49") (pintype "passive"))
    )
    (net (code "16") (name "/HS2") (class "Default")
      (node (ref "R64") (pin "2") (pinfunction "2_2") (pintype "passive"))
      (node (ref "U10") (pin "38") (pinfunction "HS2_38") (pintype "passive"))
    )
    (net (code "17") (name "/I_SENSE") (class "Default")
      (node (ref "C45") (pin "1") (pinfunction "1_1") (pintype "passive"))
      (node (ref "C55") (pin "1") (pinfunction "1_1") (pintype "passive"))
      (node (ref "C65") (pin "1") (pinfunction "1_1") (pintype "passive"))
      (node (ref "Q41") (pin "3") (pinfunction "S_3") (pintype "passive"))
      (node (ref "Q51") (pin "3") (pinfunction "S_3") (pintype "passive"))
      (node (ref "Q61") (pin "3") (pinfunction "S_3") (pintype "passive"))
      (node (ref "R00") (pin "1") (pinfunction "1_1") (pintype "passive"))
      (node (ref "R35") (pin "1") (pinfunction "1_1") (pintype "passive"))
      (node (ref "R46") (pin "2") (pinfunction "2_2") (pintype "passive"))
      (node (ref "R47") (pin "1") (pinfunction "1_1") (pintype "passive"))
      (node (ref "R49") (pin "1") (pinfunction "1_1") (pintype "passive"))
      (node (ref "R56") (pin "2") (pinfunction "2_2") (pintype "passive"))
      (node (ref "R57") (pin "1") (pinfunction "1_1") (pintype "passive"))
      (node (ref "R59") (pin "1") (pinfunction "1_1") (pintype "passive"))
      (node (ref "R66") (pin "2") (pinfunction "2_2") (pintype "passive"))
      (node (ref "R67") (pin "1") (pinfunction "1_1") (pintype "passive"))
      (node (ref "R69") (pin "1") (pinfunction "1_1") (pintype "passive"))
    )
    (net (code "18") (name "/LG0") (class "Default")
      (node (ref "D43") (pin "1") (pinfunction "C_1") (pintype "passive"))
      (node (ref "R45") (pin "2") (pinfunction "2_2") (pintype "passive"))
      (node (ref "U10") (pin "33") (pinfunction "LG0_33") (pintype "passive"))
    )
    (net (code "19") (name "/LG1") (class "Default")
      (node (ref "D53") (pin "1") (pinfunction "C_1") (pintype "passive"))
      (node (ref "R55") (pin "2") (pinfunction "2_2") (pintype "passive"))
      (node (ref "U10") (pin "45") (pinfunction "LG1_45") (pintype "passive"))
    )
    (net (code "20") (name "/LG2") (class "Default")
      (node (ref "D63") (pin "1") (pinfunction "C_1") (pintype "passive"))
      (node (ref "R65") (pin "2") (pinfunction "2_2") (pintype "passive"))
      (node (ref "U10") (pin "42") (pinfunction "LG2_42") (pintype "passive"))
    )
    (net (code "21") (name "/LS0") (class "Default")
      (node (ref "R47") (pin "2") (pinfunction "2_2") (pintype "passive"))
      (node (ref "U10") (pin "32") (pinfunction "LS0_32") (pintype "passive"))
    )
    (net (code "22") (name "/LS1") (class "Default")
      (node (ref "R57") (pin "2") (pinfunction "2_2") (pintype "passive"))
      (node (ref "U10") (pin "44") (pinfunction "LS1_44") (pintype "passive"))
    )
    (net (code "23") (name "/LS2") (class "Default")
      (node (ref "R67") (pin "2") (pinfunction "2_2") (pintype "passive"))
      (node (ref "U10") (pin "43") (pinfunction "LS2_43") (pintype "passive"))
    )
    (net (code "24") (name "/MISO_RX") (class "Default")
      (node (ref "P14") (pin "1") (pinfunction "1_1") (pintype "passive"))
      (node (ref "U10") (pin "5") (pinfunction "MISO/(RXD1)/KWS2/PS2_5") (pintype "passive"))
    )
    (net (code "25") (name "/MOSI_TX") (class "Default")
      (node (ref "P15") (pin "1") (pinfunction "1_1") (pintype "passive"))
      (node (ref "U10") (pin "6") (pinfunction "MOSI/(TXD1)/DBGEEV/KWS3/PS3_6") (pintype "passive"))
    )
    (net (code "26") (name "/PP1") (class "Default")
      (node (ref "Q76") (pin "1") (pinfunction "B_1") (pintype "passive"))
      (node (ref "R82") (pin "2") (pinfunction "2_2") (pintype "passive"))
      (node (ref "U10") (pin "61") (pinfunction "PP0/EVDD1/KWP0/(PWM0)/ECLK/FAULT5/XIRQ_61") (pintype "passive"))
    )
    (net (code "27") (name "/PWM_IN") (class "Default")
      (node (ref "C91") (pin "1") (pinfunction "1_1") (pintype "passive"))
      (node (ref "Q78") (pin "3") (pinfunction "C_3") (pintype "passive"))
      (node (ref "R84") (pin "2") (pinfunction "2_2") (pintype "passive"))
      (node (ref "T77") (pin "1") (pinfunction "1_1") (pintype "passive"))
      (node (ref "U10") (pin "52") (pinfunction "PT2/IOC2/(PWM5)/(SCK)_52") (pintype "passive"))
    )
    (net (code "28") (name "/PWM{slash}LIN") (class "Default")
      (node (ref "C27") (pin "1") (pinfunction "1_1") (pintype "passive"))
      (node (ref "C90") (pin "2") (pinfunction "2_2") (pintype "passive"))
      (node (ref "D10") (pin "1") (pinfunction "1_1") (pintype "passive"))
      (node (ref "D77") (pin "1") (pinfunction "C_1") (pintype "passive"))
      (node (ref "D80") (pin "1") (pinfunction "1_1") (pintype "passive"))
      (node (ref "J3") (pin "1") (pinfunction "1_1") (pintype "passive"))
      (node (ref "Q75") (pin "3") (pinfunction "C_3") (pintype "passive"))
      (node (ref "T74") (pin "1") (pinfunction "1_1") (pintype "passive"))
      (node (ref "U10") (pin "1") (pinfunction "LIN_1") (pintype "passive"))
    )
    (net (code "29") (name "/RST") (class "Default")
      (node (ref "C21") (pin "1") (pinfunction "1_1") (pintype "passive"))
      (node (ref "P11") (pin "1") (pinfunction "1_1") (pintype "passive"))
      (node (ref "U10") (pin "54") (pinfunction "RESET_54") (pintype "passive"))
    )
    (net (code "30") (name "/VBS0") (class "Default")
      (node (ref "C41") (pin "1") (pinfunction "1_1") (pintype "passive"))
      (node (ref "D40") (pin "2") (pinfunction "2_2") (pintype "passive"))
      (node (ref "D42") (pin "1") (pinfunction "C_1") (pintype "passive"))
      (node (ref "U10") (pin "35") (pinfunction "VBS0_35") (pintype "passive"))
    )
    (net (code "31") (name "/VBS1") (class "Default")
      (node (ref "C51") (pin "1") (pinfunction "1_1") (pintype "passive"))
      (node (ref "D50") (pin "2") (pinfunction "2_2") (pintype "passive"))
      (node (ref "D52") (pin "1") (pinfunction "C_1") (pintype "passive"))
      (node (ref "U10") (pin "47") (pinfunction "VBS1_47") (pintype "passive"))
    )
    (net (code "32") (name "/VBS2") (class "Default")
      (node (ref "C61") (pin "1") (pinfunction "1_1") (pintype "passive"))
      (node (ref "D60") (pin "2") (pinfunction "2_2") (pintype "passive"))
      (node (ref "D62") (pin "1") (pinfunction "C_1") (pintype "passive"))
      (node (ref "U10") (pin "40") (pinfunction "VBS2_40") (pintype "passive"))
    )
    (net (code "33") (name "/VCP") (class "Default")
      (node (ref "C10") (pin "1") (pinfunction "1_1") (pintype "passive"))
      (node (ref "D11") (pin "1") (pinfunction "C_1") (pintype "passive"))
      (node (ref "U10") (pin "11") (pinfunction "VCP_11") (pintype "passive"))
    )
    (net (code "34") (name "/VLS") (class "Default")
      (node (ref "C13") (pin "1") (pinfunction "1_1") (pintype "passive"))
      (node (ref "C18") (pin "2") (pinfunction "2_2") (pintype "passive"))
      (node (ref "C19") (pin "2") (pinfunction "2_2") (pintype "passive"))
      (node (ref "C20") (pin "2") (pinfunction "2_2") (pintype "passive"))
      (node (ref "D42") (pin "2") (pinfunction "A_2") (pintype "passive"))
      (node (ref "D52") (pin "2") (pinfunction "A_2") (pintype "passive"))
      (node (ref "D62") (pin "2") (pinfunction "A_2") (pintype "passive"))
      (node (ref "U10") (pin "15") (pinfunction "VLS_OUT_15") (pintype "passive"))
      (node (ref "U10") (pin "34") (pinfunction "VLS0_34") (pintype "passive"))
      (node (ref "U10") (pin "41") (pinfunction "VLS2_41") (pintype "passive"))
      (node (ref "U10") (pin "46") (pinfunction "VLS1_46") (pintype "passive"))
    )
    (net (code "35") (name "AGND") (class "Default")
      (node (ref "C17") (pin "2") (pinfunction "2_2") (pintype "passive"))
      (node (ref "R002") (pin "1") (pinfunction "1_1") (pintype "passive"))
      (node (ref "R32") (pin "1") (pinfunction "1_1") (pintype "passive"))
      (node (ref "R39") (pin "2") (pinfunction "2_2") (pintype "passive"))
      (node (ref "U10") (pin "31") (pinfunction "VSSA_31") (pintype "passive"))
    )
    (net (code "36") (name "GND") (class "Default")
      (node (ref "C13") (pin "2") (pinfunction "2_2") (pintype "passive"))
      (node (ref "C14") (pin "2") (pinfunction "2_2") (pintype "passive"))
      (node (ref "C15") (pin "2") (pinfunction "2_2") (pintype "passive"))
      (node (ref "C16") (pin "1") (pinfunction "1_1") (pintype "passive"))
      (node (ref "C18") (pin "1") (pinfunction "1_1") (pintype "passive"))
      (node (ref "C19") (pin "1") (pinfunction "1_1") (pintype "passive"))
      (node (ref "C20") (pin "1") (pinfunction "1_1") (pintype "passive"))
      (node (ref "C21") (pin "2") (pinfunction "2_2") (pintype "passive"))
      (node (ref "C22") (pin "2") (pinfunction "2_2") (pintype "passive"))
      (node (ref "C23") (pin "1") (pinfunction "1_1") (pintype "passive"))
      (node (ref "C27") (pin "2") (pinfunction "2_2") (pintype "passive"))
      (node (ref "C42") (pin "1") (pinfunction "1_1") (pintype "passive"))
      (node (ref "C52") (pin "1") (pinfunction "1_1") (pintype "passive"))
      (node (ref "C62") (pin "1") (pinfunction "1_1") (pintype "passive"))
      (node (ref "C82") (pin "1") (pinfunction "1_1") (pintype "passive"))
      (node (ref "C84") (pin "1") (pinfunction "1_1") (pintype "passive"))
      (node (ref "C90") (pin "1") (pinfunction "1_1") (pintype "passive"))
      (node (ref "C91") (pin "2") (pinfunction "2_2") (pintype "passive"))
      (node (ref "C92") (pin "2") (pinfunction "2_2") (pintype "passive"))
      (node (ref "D10") (pin "2") (pinfunction "2_2") (pintype "passive"))
      (node (ref "D40") (pin "1") (pinfunction "1_1") (pintype "passive"))
      (node (ref "D50") (pin "1") (pinfunction "1_1") (pintype "passive"))
      (node (ref "D60") (pin "1") (pinfunction "1_1") (pintype "passive"))
      (node (ref "D80") (pin "2") (pinfunction "2_2") (pintype "passive"))
      (node (ref "D81") (pin "1") (pinfunction "1_1") (pintype "passive"))
      (node (ref "P12") (pin "1") (pinfunction "1_1") (pintype "passive"))
      (node (ref "Q74") (pin "2") (pinfunction "E_2") (pintype "passive"))
      (node (ref "Q75") (pin "2") (pinfunction "E_2") (pintype "passive"))
      (node (ref "R001") (pin "2") (pinfunction "2_2") (pintype "passive"))
      (node (ref "R80") (pin "2") (pinfunction "2_2") (pintype "passive"))
      (node (ref "R84") (pin "1") (pinfunction "1_1") (pintype "passive"))
      (node (ref "R87") (pin "1") (pinfunction "1_1") (pintype "passive"))
      (node (ref "T73") (pin "1") (pinfunction "1_1") (pintype "passive"))
      (node (ref "U10") (pin "13") (pinfunction "VSSB_13") (pintype "passive"))
      (node (ref "U10") (pin "18") (pinfunction "TEST_18") (pintype "passive"))
      (node (ref "U10") (pin "19") (pinfunction "VSS2_19") (pintype "passive"))
      (node (ref "U10") (pin "57") (pinfunction "VSS1_57") (pintype "passive"))
      (node (ref "U10") (pin "63") (pinfunction "VSSX1_63") (pintype "passive"))
      (node (ref "U10") (pin "64") (pinfunction "LGND_64") (pintype "passive"))
      (node (ref "U10") (pin "65") (pinfunction "EP_PAD_65") (pintype "passive"))
    )
    (net (code "37") (name "GND_L") (class "Default")
      (node (ref "C76") (pin "1") (pinfunction "1_1") (pintype "passive"))
      (node (ref "C77") (pin "2") (pinfunction "2_2") (pintype "passive"))
      (node (ref "C78") (pin "2") (pinfunction "2_2") (pintype "passive"))
      (node (ref "C79") (pin "2") (pinfunction "2_2") (pintype "passive"))
      (node (ref "C80") (pin "2") (pinfunction "2_2") (pintype "passive"))
      (node (ref "D70") (pin "2") (pinfunction "2_2") (pintype "passive"))
      (node (ref "D71") (pin "2") (pinfunction "K_2") (pintype "passive"))
      (node (ref "Q70") (pin "3") (pinfunction "S_3") (pintype "passive"))
      (node (ref "R00") (pin "2") (pinfunction "2_2") (pintype "passive"))
      (node (ref "R001") (pin "1") (pinfunction "1_1") (pintype "passive"))
      (node (ref "R002") (pin "2") (pinfunction "2_2") (pintype "passive"))
      (node (ref "R73") (pin "1") (pinfunction "1_1") (pintype "passive"))
      (node (ref "R74") (pin "2") (pinfunction "2_2") (pintype "passive"))
    )
    (net (code "38") (name "Net-(C41-Pad2)") (class "Default")
      (node (ref "C41") (pin "2") (pinfunction "2_2") (pintype "passive"))
      (node (ref "C42") (pin "2") (pinfunction "2_2") (pintype "passive"))
      (node (ref "R43") (pin "2") (pinfunction "2_2") (pintype "passive"))
      (node (ref "R44") (pin "1") (pinfunction "1_1") (pintype "passive"))
    )
    (net (code "39") (name "Net-(C43-Pad1)") (class "Default")
      (node (ref "C43") (pin "1") (pinfunction "1_1") (pintype "passive"))
      (node (ref "R48") (pin "2") (pinfunction "2_2") (pintype "passive"))
    )
    (net (code "40") (name "Net-(C44-Pad1)") (class "Default")
      (node (ref "C44") (pin "1") (pinfunction "1_1") (pintype "passive"))
      (node (ref "R49") (pin "2") (pinfunction "2_2") (pintype "passive"))
    )
    (net (code "41") (name "Net-(C51-Pad2)") (class "Default")
      (node (ref "C51") (pin "2") (pinfunction "2_2") (pintype "passive"))
      (node (ref "C52") (pin "2") (pinfunction "2_2") (pintype "passive"))
      (node (ref "R53") (pin "2") (pinfunction "2_2") (pintype "passive"))
      (node (ref "R54") (pin "1") (pinfunction "1_1") (pintype "passive"))
    )
    (net (code "42") (name "Net-(C53-Pad1)") (class "Default")
      (node (ref "C53") (pin "1") (pinfunction "1_1") (pintype "passive"))
      (node (ref "R58") (pin "2") (pinfunction "2_2") (pintype "passive"))
    )
    (net (code "43") (name "Net-(C54-Pad1)") (class "Default")
      (node (ref "C54") (pin "1") (pinfunction "1_1") (pintype "passive"))
      (node (ref "R59") (pin "2") (pinfunction "2_2") (pintype "passive"))
    )
    (net (code "44") (name "Net-(C61-Pad2)") (class "Default")
      (node (ref "C61") (pin "2") (pinfunction "2_2") (pintype "passive"))
      (node (ref "C62") (pin "2") (pinfunction "2_2") (pintype "passive"))
      (node (ref "R63") (pin "2") (pinfunction "2_2") (pintype "passive"))
      (node (ref "R64") (pin "1") (pinfunction "1_1") (pintype "passive"))
    )
    (net (code "45") (name "Net-(C63-Pad1)") (class "Default")
      (node (ref "C63") (pin "1") (pinfunction "1_1") (pintype "passive"))
      (node (ref "R68") (pin "2") (pinfunction "2_2") (pintype "passive"))
    )
    (net (code "46") (name "Net-(C64-Pad1)") (class "Default")
      (node (ref "C64") (pin "1") (pinfunction "1_1") (pintype "passive"))
      (node (ref "R69") (pin "2") (pinfunction "2_2") (pintype "passive"))
    )
    (net (code "47") (name "Net-(C70-Pad1)") (class "Default")
      (node (ref "C70") (pin "1") (pinfunction "1_1") (pintype "passive"))
      (node (ref "C71") (pin "2") (pinfunction "2_2") (pintype "passive"))
    )
    (net (code "48") (name "Net-(C72-Pad1)") (class "Default")
      (node (ref "C72") (pin "1") (pinfunction "1_1") (pintype "passive"))
      (node (ref "C73") (pin "2") (pinfunction "2_2") (pintype "passive"))
    )
    (net (code "49") (name "Net-(C74-Pad1)") (class "Default")
      (node (ref "C74") (pin "1") (pinfunction "1_1") (pintype "passive"))
      (node (ref "C75") (pin "2") (pinfunction "2_2") (pintype "passive"))
    )
    (net (code "50") (name "Net-(C76-Pad2)") (class "Default")
      (node (ref "C76") (pin "2") (pinfunction "2_2") (pintype "passive"))
      (node (ref "R71") (pin "1") (pinfunction "1_1") (pintype "passive"))
    )
    (net (code "51") (name "Net-(C92-Pad1)") (class "Default")
      (node (ref "C92") (pin "1") (pinfunction "1_1") (pintype "passive"))
      (node (ref "L80") (pin "2") (pinfunction "2_2") (pintype "passive"))
      (node (ref "R88") (pin "2") (pinfunction "2_2") (pintype "passive"))
    )
    (net (code "52") (name "Net-(D11-A)") (class "Default")
      (node (ref "C12") (pin "1") (pinfunction "1_1") (pintype "passive"))
      (node (ref "D11") (pin "2") (pinfunction "A_2") (pintype "passive"))
      (node (ref "D12") (pin "1") (pinfunction "C_1") (pintype "passive"))
    )
    (net (code "53") (name "Net-(D41-A)") (class "Default")
      (node (ref "D41") (pin "2") (pinfunction "A_2") (pintype "passive"))
      (node (ref "Q40") (pin "1") (pinfunction "G_1") (pintype "passive"))
      (node (ref "R41") (pin "1") (pinfunction "1_1") (pintype "passive"))
      (node (ref "R42") (pin "1") (pinfunction "1_1") (pintype "passive"))
    )
    (net (code "54") (name "Net-(D43-A)") (class "Default")
      (node (ref "D43") (pin "2") (pinfunction "A_2") (pintype "passive"))
      (node (ref "Q41") (pin "1") (pinfunction "G_1") (pintype "passive"))
      (node (ref "R45") (pin "1") (pinfunction "1_1") (pintype "passive"))
      (node (ref "R46") (pin "1") (pinfunction "1_1") (pintype "passive"))
    )
    (net (code "55") (name "Net-(D51-A)") (class "Default")
      (node (ref "D51") (pin "2") (pinfunction "A_2") (pintype "passive"))
      (node (ref "Q50") (pin "1") (pinfunction "G_1") (pintype "passive"))
      (node (ref "R51") (pin "1") (pinfunction "1_1") (pintype "passive"))
      (node (ref "R52") (pin "1") (pinfunction "1_1") (pintype "passive"))
    )
    (net (code "56") (name "Net-(D53-A)") (class "Default")
      (node (ref "D53") (pin "2") (pinfunction "A_2") (pintype "passive"))
      (node (ref "Q51") (pin "1") (pinfunction "G_1") (pintype "passive"))
      (node (ref "R55") (pin "1") (pinfunction "1_1") (pintype "passive"))
      (node (ref "R56") (pin "1") (pinfunction "1_1") (pintype "passive"))
    )
    (net (code "57") (name "Net-(D61-A)") (class "Default")
      (node (ref "D61") (pin "2") (pinfunction "A_2") (pintype "passive"))
      (node (ref "Q60") (pin "1") (pinfunction "G_1") (pintype "passive"))
      (node (ref "R61") (pin "1") (pinfunction "1_1") (pintype "passive"))
      (node (ref "R62") (pin "1") (pinfunction "1_1") (pintype "passive"))
    )
    (net (code "58") (name "Net-(D63-A)") (class "Default")
      (node (ref "D63") (pin "2") (pinfunction "A_2") (pintype "passive"))
      (node (ref "Q61") (pin "1") (pinfunction "G_1") (pintype "passive"))
      (node (ref "R65") (pin "1") (pinfunction "1_1") (pintype "passive"))
      (node (ref "R66") (pin "1") (pinfunction "1_1") (pintype "passive"))
    )
    (net (code "59") (name "Net-(D71-A)") (class "Default")
      (node (ref "D71") (pin "1") (pinfunction "A_1") (pintype "passive"))
      (node (ref "Q70") (pin "1") (pinfunction "G_1") (pintype "passive"))
      (node (ref "R72") (pin "1") (pinfunction "1_1") (pintype "passive"))
      (node (ref "R73") (pin "2") (pinfunction "2_2") (pintype "passive"))
      (node (ref "R74") (pin "1") (pinfunction "1_1") (pintype "passive"))
    )
    (net (code "60") (name "Net-(D77-A)") (class "Default")
      (node (ref "D77") (pin "2") (pinfunction "A_2") (pintype "passive"))
      (node (ref "R83") (pin "2") (pinfunction "2_2") (pintype "passive"))
    )
    (net (code "61") (name "Net-(Q40-S)") (class "Default")
      (node (ref "C44") (pin "2") (pinfunction "2_2") (pintype "passive"))
      (node (ref "JP41") (pin "1") (pinfunction "1_1") (pintype "passive"))
      (node (ref "Q40") (pin "3") (pinfunction "S_3") (pintype "passive"))
      (node (ref "Q41") (pin "2") (pinfunction "D_2") (pintype "passive"))
      (node (ref "R42") (pin "2") (pinfunction "2_2") (pintype "passive"))
      (node (ref "R43") (pin "1") (pinfunction "1_1") (pintype "passive"))
      (node (ref "R48") (pin "1") (pinfunction "1_1") (pintype "passive"))
      (node (ref "T31") (pin "1") (pinfunction "1_1") (pintype "passive"))
    )
    (net (code "62") (name "Net-(Q50-S)") (class "Default")
      (node (ref "C54") (pin "2") (pinfunction "2_2") (pintype "passive"))
      (node (ref "JP51") (pin "1") (pinfunction "1_1") (pintype "passive"))
      (node (ref "Q50") (pin "3") (pinfunction "S_3") (pintype "passive"))
      (node (ref "Q51") (pin "2") (pinfunction "D_2") (pintype "passive"))
      (node (ref "R52") (pin "2") (pinfunction "2_2") (pintype "passive"))
      (node (ref "R53") (pin "1") (pinfunction "1_1") (pintype "passive"))
      (node (ref "R58") (pin "1") (pinfunction "1_1") (pintype "passive"))
      (node (ref "T34") (pin "1") (pinfunction "1_1") (pintype "passive"))
    )
    (net (code "63") (name "Net-(Q60-S)") (class "Default")
      (node (ref "C64") (pin "2") (pinfunction "2_2") (pintype "passive"))
      (node (ref "JP61") (pin "1") (pinfunction "1_1") (pintype "passive"))
      (node (ref "Q60") (pin "3") (pinfunction "S_3") (pintype "passive"))
      (node (ref "Q61") (pin "2") (pinfunction "D_2") (pintype "passive"))
      (node (ref "R62") (pin "2") (pinfunction "2_2") (pintype "passive"))
      (node (ref "R63") (pin "1") (pinfunction "1_1") (pintype "passive"))
      (node (ref "R68") (pin "1") (pinfunction "1_1") (pintype "passive"))
      (node (ref "T37") (pin "1") (pinfunction "1_1") (pintype "passive"))
    )
    (net (code "64") (name "Net-(Q74-B)") (class "Default")
      (node (ref "Q74") (pin "1") (pinfunction "B_1") (pintype "passive"))
      (node (ref "R87") (pin "2") (pinfunction "2_2") (pintype "passive"))
      (node (ref "R88") (pin "1") (pinfunction "1_1") (pintype "passive"))
    )
    (net (code "65") (name "Net-(Q75-B)") (class "Default")
      (node (ref "Q75") (pin "1") (pinfunction "B_1") (pintype "passive"))
      (node (ref "R80") (pin "1") (pinfunction "1_1") (pintype "passive"))
      (node (ref "R81") (pin "1") (pinfunction "1_1") (pintype "passive"))
    )
    (net (code "66") (name "Net-(Q76-C)") (class "Default")
      (node (ref "Q76") (pin "3") (pinfunction "C_3") (pintype "passive"))
      (node (ref "R81") (pin "2") (pinfunction "2_2") (pintype "passive"))
    )
    (net (code "67") (name "Net-(Q78-B)") (class "Default")
      (node (ref "Q78") (pin "1") (pinfunction "B_1") (pintype "passive"))
      (node (ref "R83") (pin "1") (pinfunction "1_1") (pintype "passive"))
      (node (ref "R85") (pin "1") (pinfunction "1_1") (pintype "passive"))
    )
    (net (code "68") (name "Net-(U10-VDD)") (class "Default")
      (node (ref "C16") (pin "2") (pinfunction "2_2") (pintype "passive"))
      (node (ref "U10") (pin "20") (pinfunction "VDD_20") (pintype "passive"))
    )
    (net (code "69") (name "Net-(U10-VDDF)") (class "Default")
      (node (ref "C22") (pin "1") (pinfunction "1_1") (pintype "passive"))
      (node (ref "U10") (pin "58") (pinfunction "VDDF_58") (pintype "passive"))
    )
    (net (code "70") (name "VDDA") (class "Default")
      (node (ref "C17") (pin "1") (pinfunction "1_1") (pintype "passive"))
      (node (ref "L10") (pin "1") (pinfunction "1_1") (pintype "passive"))
      (node (ref "R34") (pin "1") (pinfunction "1_1") (pintype "passive"))
      (node (ref "U10") (pin "30") (pinfunction "VDDA_30") (pintype "passive"))
    )
    (net (code "71") (name "VDDX") (class "Default")
      (node (ref "C14") (pin "1") (pinfunction "1_1") (pintype "passive"))
      (node (ref "C15") (pin "1") (pinfunction "1_1") (pintype "passive"))
      (node (ref "C23") (pin "2") (pinfunction "2_2") (pintype "passive"))
      (node (ref "L10") (pin "2") (pinfunction "2_2") (pintype "passive"))
      (node (ref "P13") (pin "1") (pinfunction "1_1") (pintype "passive"))
      (node (ref "Q76") (pin "2") (pinfunction "E_2") (pintype "passive"))
      (node (ref "Q78") (pin "2") (pinfunction "E_2") (pintype "passive"))
      (node (ref "R82") (pin "1") (pinfunction "1_1") (pintype "passive"))
      (node (ref "R85") (pin "2") (pinfunction "2_2") (pintype "passive"))
      (node (ref "R86") (pin "1") (pinfunction "1_1") (pintype "passive"))
      (node (ref "T12") (pin "1") (pinfunction "1_1") (pintype "passive"))
      (node (ref "U10") (pin "17") (pinfunction "VDDX2_17") (pintype "passive"))
      (node (ref "U10") (pin "62") (pinfunction "VDDX1_62") (pintype "passive"))
    )
    (net (code "72") (name "VSUP") (class "Default")
      (node (ref "C82") (pin "2") (pinfunction "2_2") (pintype "passive"))
      (node (ref "C84") (pin "2") (pinfunction "2_2") (pintype "passive"))
      (node (ref "D72") (pin "1") (pinfunction "C_1") (pintype "passive"))
      (node (ref "U10") (pin "16") (pinfunction "VSUP_16") (pintype "passive"))
    )
    (net (code "73") (name "unconnected-(D10-Pad3)") (class "Default")
      (node (ref "D10") (pin "3") (pinfunction "3_3") (pintype "passive"))
    )
    (net (code "74") (name "unconnected-(D40-Pad3)") (class "Default")
      (node (ref "D40") (pin "3") (pinfunction "3_3") (pintype "passive"))
    )
    (net (code "75") (name "unconnected-(D50-Pad3)") (class "Default")
      (node (ref "D50") (pin "3") (pinfunction "3_3") (pintype "passive"))
    )
    (net (code "76") (name "unconnected-(D60-Pad3)") (class "Default")
      (node (ref "D60") (pin "3") (pinfunction "3_3") (pintype "passive"))
    )
    (net (code "77") (name "unconnected-(J10-Pad1)") (class "Default")
      (node (ref "J10") (pin "1") (pintype "passive"))
    )
    (net (code "78") (name "unconnected-(J20-Pad1)") (class "Default")
      (node (ref "J20") (pin "1") (pintype "passive"))
    )
    (net (code "79") (name "unconnected-(J30-Pad1)") (class "Default")
      (node (ref "J30") (pin "1") (pintype "passive"))
    )
    (net (code "80") (name "unconnected-(J40-Pad1)") (class "Default")
      (node (ref "J40") (pin "1") (pintype "passive"))
    )
    (net (code "81") (name "unconnected-(U10-(SS)AN1_1{slash}AMP1{slash}KWAD6{slash}PAD6-Pad27)") (class "Default")
      (node (ref "U10") (pin "27") (pinfunction "(SS)AN1_1/AMP1/KWAD6/PAD6_27") (pintype "passive"))
    )
    (net (code "82") (name "unconnected-(U10-AN0_3{slash}KWAD3{slash}PAD3-Pad24)") (class "Default")
      (node (ref "U10") (pin "24") (pinfunction "AN0_3/KWAD3/PAD3_24") (pintype "passive"))
    )
    (net (code "83") (name "unconnected-(U10-AN0_4{slash}KWAD4{slash}PAD4-Pad25)") (class "Default")
      (node (ref "U10") (pin "25") (pinfunction "AN0_4/KWAD4/PAD4_25") (pintype "passive"))
    )
    (net (code "84") (name "unconnected-(U10-AN1_0{slash}AMP1{slash}KWAD5{slash}PAD6-Pad26)") (class "Default")
      (node (ref "U10") (pin "26") (pinfunction "AN1_0/AMP1/KWAD5/PAD6_26") (pintype "passive"))
    )
    (net (code "85") (name "unconnected-(U10-BCTL-Pad9)") (class "Default")
      (node (ref "U10") (pin "9") (pinfunction "BCTL_9") (pintype "passive"))
    )
    (net (code "86") (name "unconnected-(U10-BST-Pad12)") (class "Default")
      (node (ref "U10") (pin "12") (pinfunction "BST_12") (pintype "passive"))
    )
    (net (code "87") (name "unconnected-(U10-PDOCLK{slash}SCK{slash}KWS4{slash}PS4-Pad7)") (class "Default")
      (node (ref "U10") (pin "7") (pinfunction "PDOCLK/SCK/KWS4/PS4_7") (pintype "passive"))
    )
    (net (code "88") (name "unconnected-(U10-PDO{slash}SS{slash}KWS5{slash}PS5-Pad8)") (class "Default")
      (node (ref "U10") (pin "8") (pinfunction "PDO/SS/KWS5/PS5_8") (pintype "passive"))
    )
    (net (code "89") (name "unconnected-(U10-PE0{slash}EXTAL-Pad56)") (class "Default")
      (node (ref "U10") (pin "56") (pinfunction "PE0/EXTAL_56") (pintype "passive"))
    )
    (net (code "90") (name "unconnected-(U10-PE1{slash}XTAL-Pad55)") (class "Default")
      (node (ref "U10") (pin "55") (pinfunction "PE1/XTAL_55") (pintype "passive"))
    )
    (net (code "91") (name "unconnected-(U10-PP1{slash}KWP1{slash}(PWM1){slash}IRQ-Pad60)") (class "Default")
      (node (ref "U10") (pin "60") (pinfunction "PP1/KWP1/(PWM1)/IRQ_60") (pintype "passive"))
    )
    (net (code "92") (name "unconnected-(U10-PT0{slash}{slash}IOC0{slash}(PWM3){slash}ECLK{slash}FAULT5{slash}XIRQ-Pad50)") (class "Default")
      (node (ref "U10") (pin "50") (pinfunction "PT0//IOC0/(PWM3)/ECLK/FAULT5/XIRQ_50") (pintype "passive"))
    )
    (net (code "93") (name "unconnected-(U10-PT1{slash}KWP1{slash}(PWM4){slash}IRQ-Pad51)") (class "Default")
      (node (ref "U10") (pin "51") (pinfunction "PT1/KWP1/(PWM4)/IRQ_51") (pintype "passive"))
    )
    (net (code "94") (name "unconnected-(U10-PT3{slash}IOC3{slash}(SS)-Pad53)") (class "Default")
      (node (ref "U10") (pin "53") (pinfunction "PT3/IOC3/(SS)_53") (pintype "passive"))
    )
    (net (code "95") (name "unconnected-(U10-PTUT1{slash}(LPTXD){slash}TXCAN{slash}TXD1{slash}KWS1{slash}PS1-Pad4)") (class "Default")
      (node (ref "U10") (pin "4") (pinfunction "PTUT1/(LPTXD)/TXCAN/TXD1/KWS1/PS1_4") (pintype "passive"))
    )
    (net (code "96") (name "unconnected-(U10-PTUTO{slash}(LPRXD){slash}RXCAN{slash}RXD1{slash}KWS0{slash}PS0-Pad3)") (class "Default")
      (node (ref "U10") (pin "3") (pinfunction "PTUTO/(LPRXD)/RXCAN/RXD1/KWS0/PS0_3") (pintype "passive"))
    )
    (net (code "97") (name "unconnected-(U10-VRH{slash}AN1_3{slash}KWAD8{slash}PAD8-Pad29)") (class "Default")
      (node (ref "U10") (pin "29") (pinfunction "VRH/AN1_3/KWAD8/PAD8_29") (pintype "passive"))
    )
    (net (code "98") (name "unconnected-(U10-VRL{slash}AN1_2{slash}AMPP1{slash}KWAD7{slash}PAD7-Pad28)") (class "Default")
      (node (ref "U10") (pin "28") (pinfunction "VRL/AN1_2/AMPP1/KWAD7/PAD7_28") (pintype "passive"))
    )
  )
)
